# printer_v1.net
KiCad netlist of a schematic drawn in EAGLE
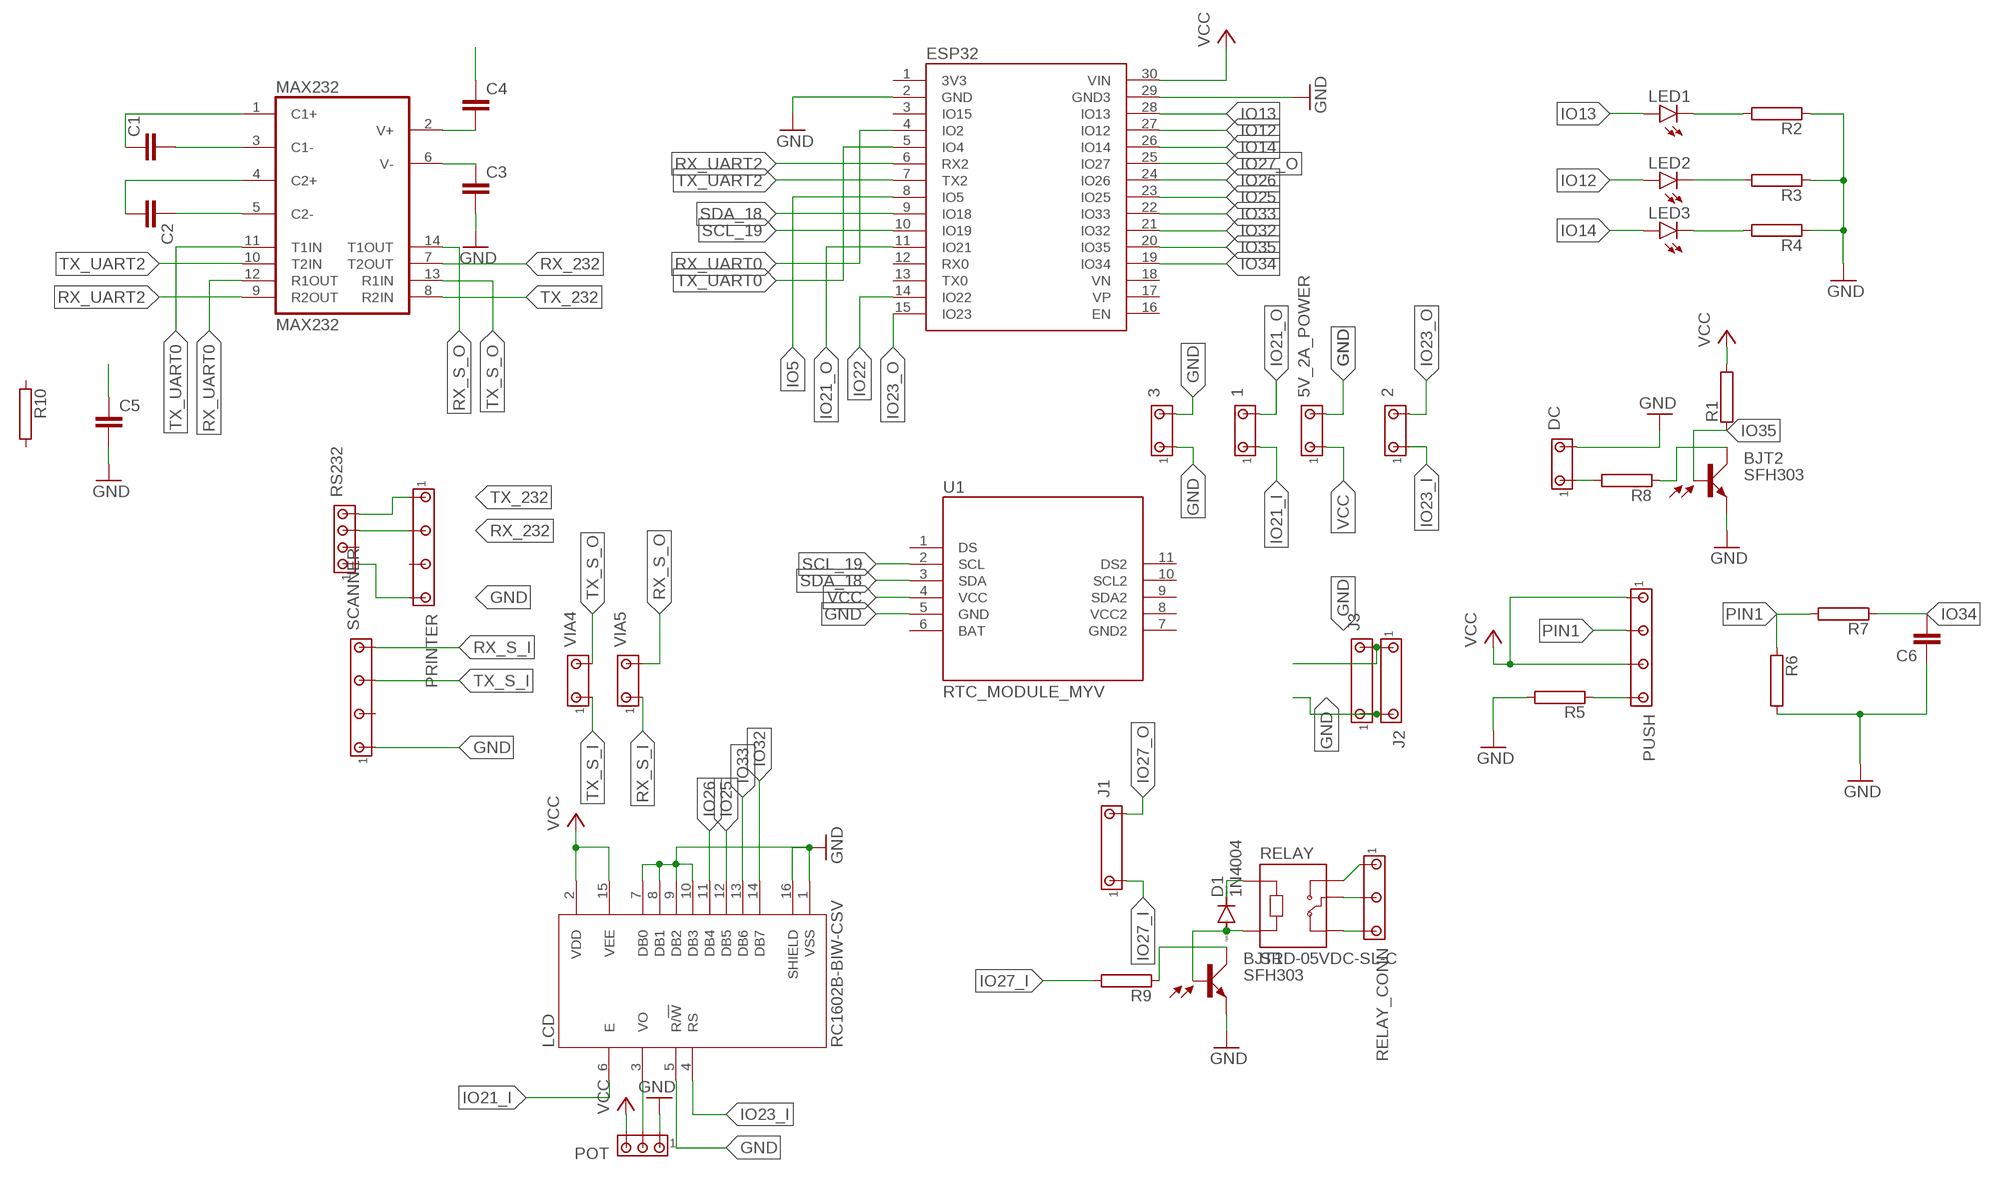
[diagram p0: schematic, sheet 1]

(export (version "E")
  (design (tool "Eeschema 10.0.6"))
  (components
    (comp (ref "1")
      (value "MTA03-100_MYV")
      (footprint "eagle-import:10X03MTA_MYV")
      (libsource (lib "eagle-import") (part "MTA03-100_MYV"))
    )
    (comp (ref "2")
      (value "MTA03-100_MYV")
      (footprint "eagle-import:10X03MTA_MYV")
      (libsource (lib "eagle-import") (part "MTA03-100_MYV"))
    )
    (comp (ref "3")
      (value "MTA03-100_MYV")
      (footprint "eagle-import:10X03MTA_MYV")
      (libsource (lib "eagle-import") (part "MTA03-100_MYV"))
    )
    (comp (ref "5V_2A_POWER")
      (value "MTA03-100_MYV")
      (footprint "eagle-import:10X03MTA_MYV")
      (libsource (lib "eagle-import") (part "MTA03-100_MYV"))
    )
    (comp (ref "BJT1")
      (value "SFH303")
      (footprint "eagle-import:SFH303")
      (libsource (lib "eagle-import") (part "SFH303"))
    )
    (comp (ref "BJT2")
      (value "SFH303")
      (footprint "eagle-import:SFH303")
      (libsource (lib "eagle-import") (part "SFH303"))
    )
    (comp (ref "C1")
      (value "C-EU025-024X044")
      (footprint "eagle-import:C025-024X044")
      (libsource (lib "eagle-import") (part "C-EU025-024X044"))
    )
    (comp (ref "C2")
      (value "C-EU025-024X044")
      (footprint "eagle-import:C025-024X044")
      (libsource (lib "eagle-import") (part "C-EU025-024X044"))
    )
    (comp (ref "C3")
      (value "C-EU025-024X044")
      (footprint "eagle-import:C025-024X044")
      (libsource (lib "eagle-import") (part "C-EU025-024X044"))
    )
    (comp (ref "C4")
      (value "C-EU025-024X044")
      (footprint "eagle-import:C025-024X044")
      (libsource (lib "eagle-import") (part "C-EU025-024X044"))
    )
    (comp (ref "C5")
      (value "C-EU025-024X044")
      (footprint "eagle-import:C025-024X044")
      (libsource (lib "eagle-import") (part "C-EU025-024X044"))
    )
    (comp (ref "C6")
      (value "C-EU025-024X044")
      (footprint "eagle-import:C025-024X044")
      (libsource (lib "eagle-import") (part "C-EU025-024X044"))
    )
    (comp (ref "D1")
      (value "1N4004")
      (footprint "eagle-import:DO41-10")
      (libsource (lib "eagle-import") (part "1N4004"))
    )
    (comp (ref "DC")
      (value "MTA03-100_MYV")
      (footprint "eagle-import:10X03MTA_MYV")
      (libsource (lib "eagle-import") (part "MTA03-100_MYV"))
    )
    (comp (ref "ESP32")
      (value "MODULE_ESP32_MYV")
      (footprint "eagle-import:MODULE_ESP32-DEVKITC-MYV")
      (libsource (lib "eagle-import") (part "MODULE_ESP32_MYV"))
    )
    (comp (ref "J1")
      (value "MTA02-LARGE_MYVSPACE1")
      (footprint "eagle-import:10X02MTA_LARGE_MYV")
      (libsource (lib "eagle-import") (part "MTA02-LARGE_MYVSPACE1"))
    )
    (comp (ref "J2")
      (value "MTA02-LARGE_MYVSPACE1")
      (footprint "eagle-import:10X02MTA_LARGE_MYV")
      (libsource (lib "eagle-import") (part "MTA02-LARGE_MYVSPACE1"))
    )
    (comp (ref "J3")
      (value "MTA02-LARGE_MYVSPACE1")
      (footprint "eagle-import:10X02MTA_LARGE_MYV")
      (libsource (lib "eagle-import") (part "MTA02-LARGE_MYVSPACE1"))
    )
    (comp (ref "LCD")
      (value "RC1602B-BIW-CSV")
      (footprint "eagle-import:LCD_RC1602B-BIW-CSV")
      (fields (field (name "MF") "Raystar"))
      (libsource (lib "eagle-import") (part "RC1602B-BIW-CSV"))
    )
    (comp (ref "LED1")
      (value "LED3MM")
      (footprint "eagle-import:LED3MM")
      (libsource (lib "eagle-import") (part "LED3MM"))
    )
    (comp (ref "LED2")
      (value "LED3MM")
      (footprint "eagle-import:LED3MM")
      (libsource (lib "eagle-import") (part "LED3MM"))
    )
    (comp (ref "LED3")
      (value "LED3MM")
      (footprint "eagle-import:LED3MM")
      (libsource (lib "eagle-import") (part "LED3MM"))
    )
    (comp (ref "MAX232")
      (value "MAX232")
      (footprint "eagle-import:DIL16")
      (fields (field (name "MF") "MAXIM") (field (name "MPN") "MAX232ACPE+"))
      (libsource (lib "eagle-import") (part "MAX232"))
    )
    (comp (ref "POT")
      (value "MTA03-100")
      (footprint "eagle-import:10X03MTA")
      (libsource (lib "eagle-import") (part "MTA03-100"))
    )
    (comp (ref "PRINTER")
      (value "MTA07-100_MYV")
      (footprint "eagle-import:10X07MTA_MYV")
      (libsource (lib "eagle-import") (part "MTA07-100_MYV"))
    )
    (comp (ref "PUSH")
      (value "MTA07-100_MYV")
      (footprint "eagle-import:10X07MTA_MYV")
      (libsource (lib "eagle-import") (part "MTA07-100_MYV"))
    )
    (comp (ref "R1")
      (value "RHPS58")
      (footprint "eagle-import:HPS58")
      (libsource (lib "eagle-import") (part "RHPS58"))
    )
    (comp (ref "R2")
      (value "RHPS58")
      (footprint "eagle-import:HPS58")
      (libsource (lib "eagle-import") (part "RHPS58"))
    )
    (comp (ref "R3")
      (value "RHPS58")
      (footprint "eagle-import:HPS58")
      (libsource (lib "eagle-import") (part "RHPS58"))
    )
    (comp (ref "R4")
      (value "RHPS58")
      (footprint "eagle-import:HPS58")
      (libsource (lib "eagle-import") (part "RHPS58"))
    )
    (comp (ref "R5")
      (value "RHPS58")
      (footprint "eagle-import:HPS58")
      (libsource (lib "eagle-import") (part "RHPS58"))
    )
    (comp (ref "R6")
      (value "RHPS58")
      (footprint "eagle-import:HPS58")
      (libsource (lib "eagle-import") (part "RHPS58"))
    )
    (comp (ref "R7")
      (value "RHPS58")
      (footprint "eagle-import:HPS58")
      (libsource (lib "eagle-import") (part "RHPS58"))
    )
    (comp (ref "R8")
      (value "RHPS58")
      (footprint "eagle-import:HPS58")
      (libsource (lib "eagle-import") (part "RHPS58"))
    )
    (comp (ref "R9")
      (value "RHPS58")
      (footprint "eagle-import:HPS58")
      (libsource (lib "eagle-import") (part "RHPS58"))
    )
    (comp (ref "R10")
      (value "RHPS58")
      (footprint "eagle-import:HPS58")
      (libsource (lib "eagle-import") (part "RHPS58"))
    )
    (comp (ref "RELAY")
      (value "SRD-05VDC-SL-C")
      (footprint "eagle-import:RELAY_SRD-05VDC-SL-C")
      (fields (field (name "MF") "Songle Relay"))
      (libsource (lib "eagle-import") (part "SRD-05VDC-SL-C"))
    )
    (comp (ref "RELAY_CONN")
      (value "MTA05-156_MYVSPACE1")
      (footprint "eagle-import:10X05MTA_MYV")
      (libsource (lib "eagle-import") (part "MTA05-156_MYVSPACE1"))
    )
    (comp (ref "RS232")
      (value "MTA04-100")
      (footprint "eagle-import:10X04MTA")
      (libsource (lib "eagle-import") (part "MTA04-100"))
    )
    (comp (ref "SCANNER")
      (value "MTA07-100_MYV")
      (footprint "eagle-import:10X07MTA_MYV")
      (libsource (lib "eagle-import") (part "MTA07-100_MYV"))
    )
    (comp (ref "U1")
      (value "RTC_MODULE_MYV")
      (footprint "eagle-import:RTC_MYV")
      (fields (field (name "MF") "Espressif Systems") (field (name "MP") "ESP32-DevKitC"))
      (libsource (lib "eagle-import") (part "RTC_MODULE_MYV"))
    )
    (comp (ref "VIA4")
      (value "MTA03-100_MYV")
      (footprint "eagle-import:10X03MTA_MYV")
      (libsource (lib "eagle-import") (part "MTA03-100_MYV"))
    )
    (comp (ref "VIA5")
      (value "MTA03-100_MYV")
      (footprint "eagle-import:10X03MTA_MYV")
      (libsource (lib "eagle-import") (part "MTA03-100_MYV"))
    )
  )
  (nets
    (net (code "1") (name "/3V3") (class "Default")
      (node (ref "ESP32") (pin "1") (pinfunction "3V3_1") (pintype "power_in"))
    )
    (net (code "2") (name "GND") (class "Default")
      (node (ref "3") (pin "1") (pinfunction "1_1") (pintype "passive"))
      (node (ref "3") (pin "3") (pinfunction "3_3") (pintype "passive"))
      (node (ref "5V_2A_POWER") (pin "3") (pinfunction "3_3") (pintype "passive"))
      (node (ref "BJT1") (pin "1") (pinfunction "E_1") (pintype "passive"))
      (node (ref "BJT2") (pin "1") (pinfunction "E_1") (pintype "passive"))
      (node (ref "C3") (pin "2") (pinfunction "2_2") (pintype "passive"))
      (node (ref "C5") (pin "2") (pinfunction "2_2") (pintype "passive"))
      (node (ref "C6") (pin "1") (pinfunction "1_1") (pintype "passive"))
      (node (ref "DC") (pin "3") (pinfunction "3_3") (pintype "passive"))
      (node (ref "ESP32") (pin "2") (pinfunction "GND_2") (pintype "input"))
      (node (ref "ESP32") (pin "29") (pinfunction "GND3_29") (pintype "power_in"))
      (node (ref "J2") (pin "1") (pinfunction "1_1") (pintype "passive"))
      (node (ref "J2") (pin "5") (pinfunction "5_5") (pintype "passive"))
      (node (ref "J3") (pin "1") (pinfunction "1_1") (pintype "passive"))
      (node (ref "J3") (pin "5") (pinfunction "5_5") (pintype "passive"))
      (node (ref "LCD") (pin "1") (pinfunction "VSS_1") (pintype "power_in"))
      (node (ref "LCD") (pin "10") (pinfunction "DB3_10") (pintype "bidirectional"))
      (node (ref "LCD") (pin "16") (pinfunction "SHIELD_16") (pintype "passive"))
      (node (ref "LCD") (pin "5") (pinfunction "R/~{W}_5") (pintype "bidirectional"))
      (node (ref "LCD") (pin "7") (pinfunction "DB0_7") (pintype "bidirectional"))
      (node (ref "LCD") (pin "8") (pinfunction "DB1_8") (pintype "bidirectional"))
      (node (ref "LCD") (pin "9") (pinfunction "DB2_9") (pintype "bidirectional"))
      (node (ref "POT") (pin "1") (pinfunction "1_1") (pintype "passive"))
      (node (ref "PRINTER") (pin "7") (pinfunction "7_7") (pintype "passive"))
      (node (ref "R2") (pin "1") (pinfunction "1_1") (pintype "passive"))
      (node (ref "R3") (pin "1") (pinfunction "1_1") (pintype "passive"))
      (node (ref "R4") (pin "1") (pinfunction "1_1") (pintype "passive"))
      (node (ref "R5") (pin "2") (pinfunction "2_2") (pintype "passive"))
      (node (ref "R6") (pin "2") (pinfunction "2_2") (pintype "passive"))
      (node (ref "RS232") (pin "1") (pinfunction "1_1") (pintype "passive"))
      (node (ref "SCANNER") (pin "1") (pinfunction "1_1") (pintype "passive"))
      (node (ref "U1") (pin "5") (pinfunction "GND_5") (pintype "bidirectional"))
    )
    (net (code "3") (name "IO5") (class "Default")
      (node (ref "ESP32") (pin "8") (pinfunction "IO5_8") (pintype "bidirectional"))
    )
    (net (code "4") (name "IO12") (class "Default")
      (node (ref "ESP32") (pin "27") (pinfunction "IO12_27") (pintype "bidirectional"))
      (node (ref "LED2") (pin "A") (pinfunction "A_A") (pintype "passive"))
    )
    (net (code "5") (name "IO13") (class "Default")
      (node (ref "ESP32") (pin "28") (pinfunction "IO13_28") (pintype "bidirectional"))
      (node (ref "LED1") (pin "A") (pinfunction "A_A") (pintype "passive"))
    )
    (net (code "6") (name "IO14") (class "Default")
      (node (ref "ESP32") (pin "26") (pinfunction "IO14_26") (pintype "input"))
      (node (ref "LED3") (pin "A") (pinfunction "A_A") (pintype "passive"))
    )
    (net (code "7") (name "IO21_I") (class "Default")
      (node (ref "1") (pin "1") (pinfunction "1_1") (pintype "passive"))
      (node (ref "LCD") (pin "6") (pinfunction "E_6") (pintype "input"))
    )
    (net (code "8") (name "IO21_O") (class "Default")
      (node (ref "1") (pin "3") (pinfunction "3_3") (pintype "passive"))
      (node (ref "ESP32") (pin "11") (pinfunction "IO21_11") (pintype "bidirectional"))
    )
    (net (code "9") (name "IO22") (class "Default")
      (node (ref "ESP32") (pin "14") (pinfunction "IO22_14") (pintype "bidirectional"))
    )
    (net (code "10") (name "IO23_I") (class "Default")
      (node (ref "2") (pin "1") (pinfunction "1_1") (pintype "passive"))
      (node (ref "LCD") (pin "4") (pinfunction "RS_4") (pintype "bidirectional"))
    )
    (net (code "11") (name "IO23_O") (class "Default")
      (node (ref "2") (pin "3") (pinfunction "3_3") (pintype "passive"))
      (node (ref "ESP32") (pin "15") (pinfunction "IO23_15") (pintype "bidirectional"))
    )
    (net (code "12") (name "IO25") (class "Default")
      (node (ref "ESP32") (pin "23") (pinfunction "IO25_23") (pintype "bidirectional"))
      (node (ref "LCD") (pin "12") (pinfunction "DB5_12") (pintype "bidirectional"))
    )
    (net (code "13") (name "IO26") (class "Default")
      (node (ref "ESP32") (pin "24") (pinfunction "IO26_24") (pintype "bidirectional"))
      (node (ref "LCD") (pin "11") (pinfunction "DB4_11") (pintype "bidirectional"))
    )
    (net (code "14") (name "IO27_I") (class "Default")
      (node (ref "J1") (pin "1") (pinfunction "1_1") (pintype "passive"))
      (node (ref "R9") (pin "2") (pinfunction "2_2") (pintype "passive"))
    )
    (net (code "15") (name "IO27_O") (class "Default")
      (node (ref "ESP32") (pin "25") (pinfunction "IO27_25") (pintype "bidirectional"))
      (node (ref "J1") (pin "5") (pinfunction "5_5") (pintype "passive"))
    )
    (net (code "16") (name "IO32") (class "Default")
      (node (ref "ESP32") (pin "21") (pinfunction "IO32_21") (pintype "bidirectional"))
      (node (ref "LCD") (pin "14") (pinfunction "DB7_14") (pintype "bidirectional"))
    )
    (net (code "17") (name "IO33") (class "Default")
      (node (ref "ESP32") (pin "22") (pinfunction "IO33_22") (pintype "bidirectional"))
      (node (ref "LCD") (pin "13") (pinfunction "DB6_13") (pintype "bidirectional"))
    )
    (net (code "18") (name "IO34") (class "Default")
      (node (ref "C6") (pin "2") (pinfunction "2_2") (pintype "passive"))
      (node (ref "ESP32") (pin "19") (pinfunction "IO34_19") (pintype "bidirectional"))
      (node (ref "R7") (pin "1") (pinfunction "1_1") (pintype "passive"))
    )
    (net (code "19") (name "IO35") (class "Default")
      (node (ref "BJT2") (pin "3") (pinfunction "B_3") (pintype "passive"))
      (node (ref "ESP32") (pin "20") (pinfunction "IO35_20") (pintype "bidirectional"))
      (node (ref "R1") (pin "1") (pinfunction "1_1") (pintype "passive"))
    )
    (net (code "20") (name "Net-(BJT1-B)") (class "Default")
      (node (ref "BJT1") (pin "3") (pinfunction "B_3") (pintype "passive"))
      (node (ref "D1") (pin "A") (pinfunction "A_A") (pintype "passive"))
      (node (ref "RELAY") (pin "A2") (pinfunction "A2_A2") (pintype "passive"))
    )
    (net (code "21") (name "Net-(BJT1-C)") (class "Default")
      (node (ref "BJT1") (pin "2") (pinfunction "C_2") (pintype "passive"))
      (node (ref "R9") (pin "1") (pinfunction "1_1") (pintype "passive"))
    )
    (net (code "22") (name "Net-(BJT2-C)") (class "Default")
      (node (ref "BJT2") (pin "2") (pinfunction "C_2") (pintype "passive"))
      (node (ref "R8") (pin "1") (pinfunction "1_1") (pintype "passive"))
    )
    (net (code "23") (name "Net-(D1-PadC)") (class "Default")
      (node (ref "D1") (pin "C") (pinfunction "C_C") (pintype "passive"))
      (node (ref "RELAY") (pin "A1") (pinfunction "A1_A1") (pintype "passive"))
    )
    (net (code "24") (name "Net-(DC-Pad1)") (class "Default")
      (node (ref "DC") (pin "1") (pinfunction "1_1") (pintype "passive"))
      (node (ref "R8") (pin "2") (pinfunction "2_2") (pintype "passive"))
    )
    (net (code "25") (name "Net-(LCD-VO)") (class "Default")
      (node (ref "LCD") (pin "3") (pinfunction "VO_3") (pintype "input"))
      (node (ref "POT") (pin "2") (pinfunction "2_2") (pintype "passive"))
    )
    (net (code "26") (name "Net-(LED1-C)") (class "Default")
      (node (ref "LED1") (pin "K") (pinfunction "C_K") (pintype "passive"))
      (node (ref "R2") (pin "2") (pinfunction "2_2") (pintype "passive"))
    )
    (net (code "27") (name "Net-(LED2-C)") (class "Default")
      (node (ref "LED2") (pin "K") (pinfunction "C_K") (pintype "passive"))
      (node (ref "R3") (pin "2") (pinfunction "2_2") (pintype "passive"))
    )
    (net (code "28") (name "Net-(LED3-C)") (class "Default")
      (node (ref "LED3") (pin "K") (pinfunction "C_K") (pintype "passive"))
      (node (ref "R4") (pin "2") (pinfunction "2_2") (pintype "passive"))
    )
    (net (code "29") (name "Net-(MAX232A-C1+)") (class "Default")
      (node (ref "C1") (pin "1") (pinfunction "1_1") (pintype "passive"))
      (node (ref "MAX232") (pin "1") (pinfunction "C1+_1") (pintype "bidirectional"))
    )
    (net (code "30") (name "Net-(MAX232A-C1-)") (class "Default")
      (node (ref "C1") (pin "2") (pinfunction "2_2") (pintype "passive"))
      (node (ref "MAX232") (pin "3") (pinfunction "C1-_3") (pintype "bidirectional"))
    )
    (net (code "31") (name "Net-(MAX232A-C2+)") (class "Default")
      (node (ref "C2") (pin "2") (pinfunction "2_2") (pintype "passive"))
      (node (ref "MAX232") (pin "4") (pinfunction "C2+_4") (pintype "bidirectional"))
    )
    (net (code "32") (name "Net-(MAX232A-C2-)") (class "Default")
      (node (ref "C2") (pin "1") (pinfunction "1_1") (pintype "passive"))
      (node (ref "MAX232") (pin "5") (pinfunction "C2-_5") (pintype "bidirectional"))
    )
    (net (code "33") (name "Net-(MAX232A-V+)") (class "Default")
      (node (ref "C4") (pin "2") (pinfunction "2_2") (pintype "passive"))
      (node (ref "MAX232") (pin "2") (pinfunction "V+_2") (pintype "bidirectional"))
    )
    (net (code "34") (name "Net-(MAX232A-V-)") (class "Default")
      (node (ref "C3") (pin "1") (pinfunction "1_1") (pintype "passive"))
      (node (ref "MAX232") (pin "6") (pinfunction "V-_6") (pintype "bidirectional"))
    )
    (net (code "35") (name "Net-(PUSH-Pad7)") (class "Default")
      (node (ref "PUSH") (pin "7") (pinfunction "7_7") (pintype "passive"))
      (node (ref "R5") (pin "1") (pinfunction "1_1") (pintype "passive"))
    )
    (net (code "36") (name "Net-(RELAY-PadCOM)") (class "Default")
      (node (ref "RELAY") (pin "COM") (pinfunction "COM_COM") (pintype "passive"))
      (node (ref "RELAY_CONN") (pin "3") (pinfunction "3_3") (pintype "passive"))
    )
    (net (code "37") (name "Net-(RELAY-PadNC)") (class "Default")
      (node (ref "RELAY") (pin "NC") (pinfunction "NC_NC") (pintype "passive"))
      (node (ref "RELAY_CONN") (pin "5") (pinfunction "5_5") (pintype "passive"))
    )
    (net (code "38") (name "Net-(RELAY-PadNO)") (class "Default")
      (node (ref "RELAY") (pin "NO") (pinfunction "NO_NO") (pintype "passive"))
      (node (ref "RELAY_CONN") (pin "1") (pinfunction "1_1") (pintype "passive"))
    )
    (net (code "39") (name "PIN1") (class "Default")
      (node (ref "PUSH") (pin "3") (pinfunction "3_3") (pintype "passive"))
      (node (ref "R6") (pin "1") (pinfunction "1_1") (pintype "passive"))
      (node (ref "R7") (pin "2") (pinfunction "2_2") (pintype "passive"))
    )
    (net (code "40") (name "RX_232") (class "Default")
      (node (ref "MAX232") (pin "7") (pinfunction "T2OUT_7") (pintype "output"))
      (node (ref "PRINTER") (pin "3") (pinfunction "3_3") (pintype "passive"))
      (node (ref "RS232") (pin "3") (pinfunction "3_3") (pintype "passive"))
    )
    (net (code "41") (name "RX_S_I") (class "Default")
      (node (ref "SCANNER") (pin "7") (pinfunction "7_7") (pintype "passive"))
      (node (ref "VIA5") (pin "1") (pinfunction "1_1") (pintype "passive"))
    )
    (net (code "42") (name "RX_S_O") (class "Default")
      (node (ref "MAX232") (pin "14") (pinfunction "T1OUT_14") (pintype "output"))
      (node (ref "VIA5") (pin "3") (pinfunction "3_3") (pintype "passive"))
    )
    (net (code "43") (name "RX_UART0") (class "Default")
      (node (ref "ESP32") (pin "4") (pinfunction "IO2_4") (pintype "input"))
      (node (ref "MAX232") (pin "12") (pinfunction "R1OUT_12") (pintype "output"))
    )
    (net (code "44") (name "RX_UART2") (class "Default")
      (node (ref "ESP32") (pin "6") (pinfunction "RX2_6") (pintype "bidirectional"))
      (node (ref "MAX232") (pin "9") (pinfunction "R2OUT_9") (pintype "output"))
    )
    (net (code "45") (name "SCL_19") (class "Default")
      (node (ref "ESP32") (pin "10") (pinfunction "IO19_10") (pintype "bidirectional"))
      (node (ref "U1") (pin "2") (pinfunction "SCL_2") (pintype "bidirectional"))
    )
    (net (code "46") (name "SDA_18") (class "Default")
      (node (ref "ESP32") (pin "9") (pinfunction "IO18_9") (pintype "bidirectional"))
      (node (ref "U1") (pin "3") (pinfunction "SDA_3") (pintype "bidirectional"))
    )
    (net (code "47") (name "TX_232") (class "Default")
      (node (ref "MAX232") (pin "8") (pinfunction "R2IN_8") (pintype "input"))
      (node (ref "PRINTER") (pin "1") (pinfunction "1_1") (pintype "passive"))
      (node (ref "RS232") (pin "4") (pinfunction "4_4") (pintype "passive"))
    )
    (net (code "48") (name "TX_S_I") (class "Default")
      (node (ref "SCANNER") (pin "5") (pinfunction "5_5") (pintype "passive"))
      (node (ref "VIA4") (pin "1") (pinfunction "1_1") (pintype "passive"))
    )
    (net (code "49") (name "TX_S_O") (class "Default")
      (node (ref "MAX232") (pin "13") (pinfunction "R1IN_13") (pintype "input"))
      (node (ref "VIA4") (pin "3") (pinfunction "3_3") (pintype "passive"))
    )
    (net (code "50") (name "TX_UART0") (class "Default")
      (node (ref "ESP32") (pin "5") (pinfunction "IO4_5") (pintype "bidirectional"))
      (node (ref "MAX232") (pin "11") (pinfunction "T1IN_11") (pintype "input"))
    )
    (net (code "51") (name "TX_UART2") (class "Default")
      (node (ref "ESP32") (pin "7") (pinfunction "TX2_7") (pintype "bidirectional"))
      (node (ref "MAX232") (pin "10") (pinfunction "T2IN_10") (pintype "input"))
    )
    (net (code "52") (name "VCC") (class "Default")
      (node (ref "5V_2A_POWER") (pin "1") (pinfunction "1_1") (pintype "passive"))
      (node (ref "ESP32") (pin "30") (pinfunction "VIN_30") (pintype "power_in"))
      (node (ref "LCD") (pin "15") (pinfunction "VEE_15") (pintype "output"))
      (node (ref "LCD") (pin "2") (pinfunction "VDD_2") (pintype "power_in"))
      (node (ref "POT") (pin "3") (pinfunction "3_3") (pintype "passive"))
      (node (ref "PUSH") (pin "1") (pinfunction "1_1") (pintype "passive"))
      (node (ref "PUSH") (pin "5") (pinfunction "5_5") (pintype "passive"))
      (node (ref "R1") (pin "2") (pinfunction "2_2") (pintype "passive"))
      (node (ref "U1") (pin "4") (pinfunction "VCC_4") (pintype "bidirectional"))
    )
    (net (code "53") (name "unconnected-(C4-Pad1)") (class "Default")
      (node (ref "C4") (pin "1") (pinfunction "1_1") (pintype "passive"))
    )
    (net (code "54") (name "unconnected-(C5-Pad1)") (class "Default")
      (node (ref "C5") (pin "1") (pinfunction "1_1") (pintype "passive"))
    )
    (net (code "55") (name "unconnected-(ESP32-EN-Pad16)") (class "Default")
      (node (ref "ESP32") (pin "16") (pinfunction "EN_16") (pintype "bidirectional"))
    )
    (net (code "56") (name "unconnected-(ESP32-IO15-Pad3)") (class "Default")
      (node (ref "ESP32") (pin "3") (pinfunction "IO15_3") (pintype "input"))
    )
    (net (code "57") (name "unconnected-(ESP32-RX0-Pad12)") (class "Default")
      (node (ref "ESP32") (pin "12") (pinfunction "RX0_12") (pintype "bidirectional"))
    )
    (net (code "58") (name "unconnected-(ESP32-TX0-Pad13)") (class "Default")
      (node (ref "ESP32") (pin "13") (pinfunction "TX0_13") (pintype "bidirectional"))
    )
    (net (code "59") (name "unconnected-(ESP32-VN-Pad18)") (class "Default")
      (node (ref "ESP32") (pin "18") (pinfunction "VN_18") (pintype "bidirectional"))
    )
    (net (code "60") (name "unconnected-(ESP32-VP-Pad17)") (class "Default")
      (node (ref "ESP32") (pin "17") (pinfunction "VP_17") (pintype "bidirectional"))
    )
    (net (code "61") (name "unconnected-(PRINTER-Pad5)") (class "Default")
      (node (ref "PRINTER") (pin "5") (pinfunction "5_5") (pintype "passive"))
    )
    (net (code "62") (name "unconnected-(R10-Pad1)") (class "Default")
      (node (ref "R10") (pin "1") (pinfunction "1_1") (pintype "passive"))
    )
    (net (code "63") (name "unconnected-(R10-Pad2)") (class "Default")
      (node (ref "R10") (pin "2") (pinfunction "2_2") (pintype "passive"))
    )
    (net (code "64") (name "unconnected-(RS232-Pad2)") (class "Default")
      (node (ref "RS232") (pin "2") (pinfunction "2_2") (pintype "passive"))
    )
    (net (code "65") (name "unconnected-(SCANNER-Pad3)") (class "Default")
      (node (ref "SCANNER") (pin "3") (pinfunction "3_3") (pintype "passive"))
    )
    (net (code "66") (name "unconnected-(U1-BAT-Pad6)") (class "Default")
      (node (ref "U1") (pin "6") (pinfunction "BAT_6") (pintype "bidirectional"))
    )
    (net (code "67") (name "unconnected-(U1-DS-Pad1)") (class "Default")
      (node (ref "U1") (pin "1") (pinfunction "DS_1") (pintype "bidirectional"))
    )
    (net (code "68") (name "unconnected-(U1-DS2-Pad11)") (class "Default")
      (node (ref "U1") (pin "11") (pinfunction "DS2_11") (pintype "bidirectional"))
    )
    (net (code "69") (name "unconnected-(U1-GND2-Pad7)") (class "Default")
      (node (ref "U1") (pin "7") (pinfunction "GND2_7") (pintype "bidirectional"))
    )
    (net (code "70") (name "unconnected-(U1-SCL2-Pad10)") (class "Default")
      (node (ref "U1") (pin "10") (pinfunction "SCL2_10") (pintype "bidirectional"))
    )
    (net (code "71") (name "unconnected-(U1-SDA2-Pad9)") (class "Default")
      (node (ref "U1") (pin "9") (pinfunction "SDA2_9") (pintype "bidirectional"))
    )
    (net (code "72") (name "unconnected-(U1-VCC2-Pad8)") (class "Default")
      (node (ref "U1") (pin "8") (pinfunction "VCC2_8") (pintype "bidirectional"))
    )
  )
)
